# FLODAR_V3.net
KiCad netlist of a schematic drawn in EAGLE
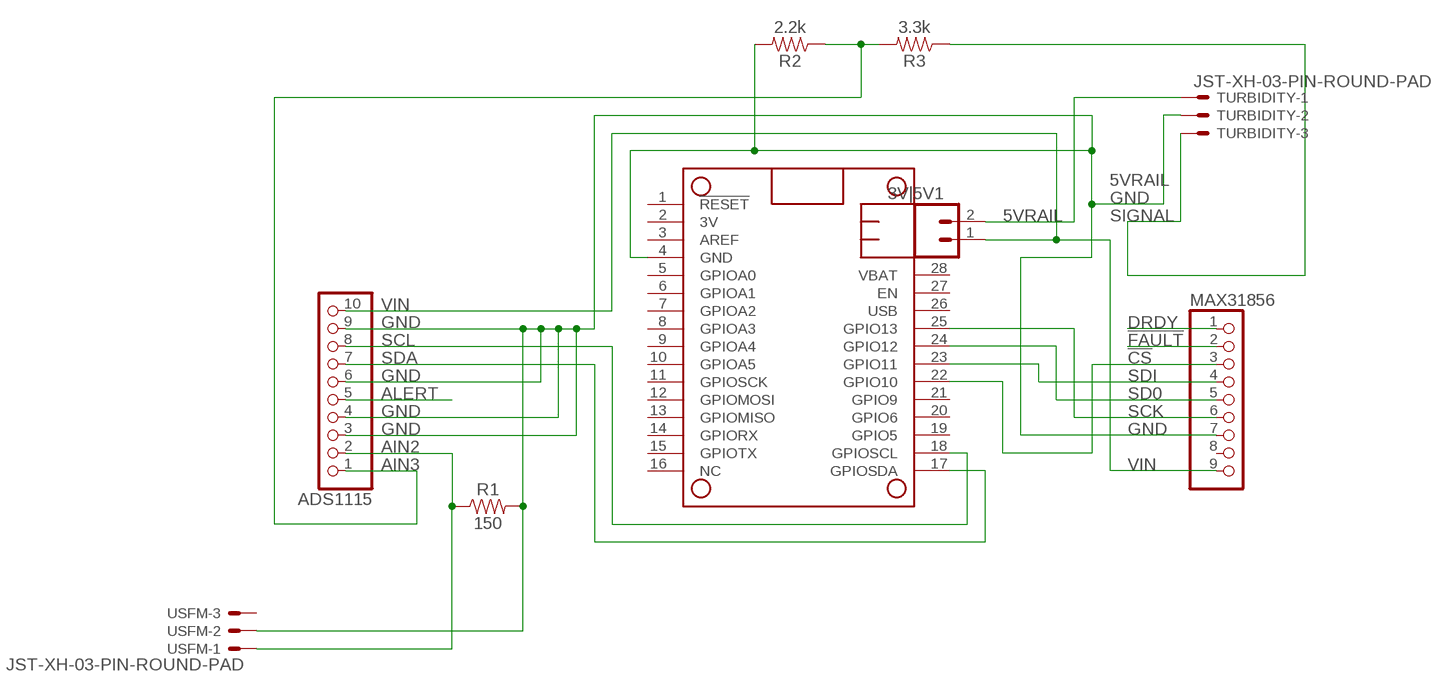
[diagram p0: schematic, sheet 1]

(export (version "E")
  (design (tool "Eeschema 10.0.6"))
  (components
    (comp (ref "3V|5V1")
      (value "CONN_021X02_NO_SILK")
      (footprint "eagle-import:1X02_NO_SILK")
      (libsource (lib "eagle-import") (part "CONN_021X02_NO_SILK"))
    )
    (comp (ref "ADS1115")
      (value "HEADER-1X1070MIL")
      (footprint "eagle-import:1X10_ROUND70")
      (libsource (lib "eagle-import") (part "HEADER-1X1070MIL"))
    )
    (comp (ref "MAX31856")
      (value "HEADER-1X970MIL")
      (footprint "eagle-import:1X09_ROUND_70")
      (libsource (lib "eagle-import") (part "HEADER-1X970MIL"))
    )
    (comp (ref "MS3")
      (value "FEATHERWING")
      (footprint "eagle-import:FEATHERWING")
      (libsource (lib "eagle-import") (part "FEATHERWING"))
    )
    (comp (ref "R1")
      (value "150")
      (footprint "eagle-import:0603")
      (libsource (lib "eagle-import") (part "150OHM-0603-1/10W-1%"))
    )
    (comp (ref "R2")
      (value "2.2k")
      (footprint "eagle-import:0603")
      (libsource (lib "eagle-import") (part "2.2KOHM-0603-1/10W-1%"))
    )
    (comp (ref "R3")
      (value "3.3k")
      (footprint "eagle-import:0603")
      (libsource (lib "eagle-import") (part "3.3KOHM-0603-1/10W-1%"))
    )
    (comp (ref "TURBIDITY")
      (value "JST-XH-03-PIN-ROUND-PAD")
      (footprint "eagle-import:JST-XH-03-PACKAGE-ROUND-PAD")
      (libsource (lib "eagle-import") (part "JST-XH-03-PIN-ROUND-PAD"))
    )
    (comp (ref "USFM")
      (value "JST-XH-03-PIN-ROUND-PAD")
      (footprint "eagle-import:JST-XH-03-PACKAGE-ROUND-PAD")
      (libsource (lib "eagle-import") (part "JST-XH-03-PIN-ROUND-PAD"))
    )
  )
  (nets
    (net (code "1") (name "/3V") (class "Default")
      (node (ref "MS3") (pin "2") (pinfunction "3V_2") (pintype "power_in"))
    )
    (net (code "2") (name "/5VRAIL") (class "Default")
      (node (ref "3V|5V1") (pin "2") (pinfunction "2_2") (pintype "passive"))
      (node (ref "TURBIDITY") (pin "1") (pinfunction "S_1") (pintype "passive"))
    )
    (net (code "3") (name "/AIN2") (class "Default")
      (node (ref "ADS1115") (pin "2") (pinfunction "2_2") (pintype "passive"))
      (node (ref "R1") (pin "1") (pinfunction "1_1") (pintype "passive"))
      (node (ref "USFM") (pin "1") (pinfunction "S_1") (pintype "passive"))
    )
    (net (code "4") (name "/AIN3") (class "Default")
      (node (ref "ADS1115") (pin "1") (pinfunction "1_1") (pintype "passive"))
      (node (ref "R2") (pin "1") (pinfunction "1_1") (pintype "passive"))
      (node (ref "R3") (pin "2") (pinfunction "2_2") (pintype "passive"))
    )
    (net (code "5") (name "/ALERT") (class "Default")
      (node (ref "ADS1115") (pin "5") (pinfunction "5_5") (pintype "passive"))
    )
    (net (code "6") (name "/DRDY") (class "Default")
      (node (ref "MAX31856") (pin "1") (pinfunction "1_1") (pintype "passive"))
    )
    (net (code "7") (name "/GND") (class "Default")
      (node (ref "ADS1115") (pin "3") (pinfunction "3_3") (pintype "passive"))
      (node (ref "ADS1115") (pin "4") (pinfunction "4_4") (pintype "passive"))
      (node (ref "ADS1115") (pin "6") (pinfunction "6_6") (pintype "passive"))
      (node (ref "ADS1115") (pin "9") (pinfunction "9_9") (pintype "passive"))
      (node (ref "MAX31856") (pin "7") (pinfunction "7_7") (pintype "passive"))
      (node (ref "MS3") (pin "4") (pinfunction "GND_4") (pintype "power_in"))
      (node (ref "R1") (pin "2") (pinfunction "2_2") (pintype "passive"))
      (node (ref "R2") (pin "2") (pinfunction "2_2") (pintype "passive"))
      (node (ref "TURBIDITY") (pin "2") (pinfunction "S_2") (pintype "passive"))
      (node (ref "USFM") (pin "2") (pinfunction "S_2") (pintype "passive"))
    )
    (net (code "8") (name "/SCK") (class "Default")
      (node (ref "MAX31856") (pin "6") (pinfunction "6_6") (pintype "passive"))
      (node (ref "MS3") (pin "25") (pinfunction "GPIO13_25") (pintype "bidirectional"))
    )
    (net (code "9") (name "/SCL") (class "Default")
      (node (ref "ADS1115") (pin "8") (pinfunction "8_8") (pintype "passive"))
      (node (ref "MS3") (pin "18") (pinfunction "GPIOSCL_18") (pintype "bidirectional"))
    )
    (net (code "10") (name "/SD0") (class "Default")
      (node (ref "MAX31856") (pin "5") (pinfunction "5_5") (pintype "passive"))
      (node (ref "MS3") (pin "24") (pinfunction "GPIO12_24") (pintype "bidirectional"))
    )
    (net (code "11") (name "/SDA") (class "Default")
      (node (ref "ADS1115") (pin "7") (pinfunction "7_7") (pintype "passive"))
      (node (ref "MS3") (pin "17") (pinfunction "GPIOSDA_17") (pintype "bidirectional"))
    )
    (net (code "12") (name "/SDI") (class "Default")
      (node (ref "MAX31856") (pin "4") (pinfunction "4_4") (pintype "passive"))
      (node (ref "MS3") (pin "23") (pinfunction "GPIO11_23") (pintype "bidirectional"))
    )
    (net (code "13") (name "/SIGNAL") (class "Default")
      (node (ref "R3") (pin "1") (pinfunction "1_1") (pintype "passive"))
      (node (ref "TURBIDITY") (pin "3") (pinfunction "S_3") (pintype "passive"))
    )
    (net (code "14") (name "/USB") (class "Default")
      (node (ref "MS3") (pin "26") (pinfunction "USB_26") (pintype "power_in"))
    )
    (net (code "15") (name "/VBAT") (class "Default")
      (node (ref "MS3") (pin "28") (pinfunction "VBAT_28") (pintype "power_in"))
    )
    (net (code "16") (name "/VIN") (class "Default")
      (node (ref "3V|5V1") (pin "1") (pinfunction "1_1") (pintype "passive"))
      (node (ref "ADS1115") (pin "10") (pinfunction "10_10") (pintype "passive"))
      (node (ref "MAX31856") (pin "9") (pinfunction "9_9") (pintype "passive"))
    )
    (net (code "17") (name "/~{CS}") (class "Default")
      (node (ref "MAX31856") (pin "3") (pinfunction "3_3") (pintype "passive"))
      (node (ref "MS3") (pin "22") (pinfunction "GPIO10_22") (pintype "bidirectional"))
    )
    (net (code "18") (name "/~{FAULT}") (class "Default")
      (node (ref "MAX31856") (pin "2") (pinfunction "2_2") (pintype "passive"))
    )
    (net (code "19") (name "unconnected-(MAX31856-Pad8)") (class "Default")
      (node (ref "MAX31856") (pin "8") (pinfunction "8_8") (pintype "passive"))
    )
    (net (code "20") (name "unconnected-(MS3-AREF-Pad3)") (class "Default")
      (node (ref "MS3") (pin "3") (pinfunction "AREF_3") (pintype "passive"))
    )
    (net (code "21") (name "unconnected-(MS3-EN-Pad27)") (class "Default")
      (node (ref "MS3") (pin "27") (pinfunction "EN_27") (pintype "passive"))
    )
    (net (code "22") (name "unconnected-(MS3-GPIO5-Pad19)") (class "Default")
      (node (ref "MS3") (pin "19") (pinfunction "GPIO5_19") (pintype "bidirectional"))
    )
    (net (code "23") (name "unconnected-(MS3-GPIO6-Pad20)") (class "Default")
      (node (ref "MS3") (pin "20") (pinfunction "GPIO6_20") (pintype "bidirectional"))
    )
    (net (code "24") (name "unconnected-(MS3-GPIO9-Pad21)") (class "Default")
      (node (ref "MS3") (pin "21") (pinfunction "GPIO9_21") (pintype "bidirectional"))
    )
    (net (code "25") (name "unconnected-(MS3-GPIOA0-Pad5)") (class "Default")
      (node (ref "MS3") (pin "5") (pinfunction "GPIOA0_5") (pintype "bidirectional"))
    )
    (net (code "26") (name "unconnected-(MS3-GPIOA1-Pad6)") (class "Default")
      (node (ref "MS3") (pin "6") (pinfunction "GPIOA1_6") (pintype "bidirectional"))
    )
    (net (code "27") (name "unconnected-(MS3-GPIOA2-Pad7)") (class "Default")
      (node (ref "MS3") (pin "7") (pinfunction "GPIOA2_7") (pintype "bidirectional"))
    )
    (net (code "28") (name "unconnected-(MS3-GPIOA3-Pad8)") (class "Default")
      (node (ref "MS3") (pin "8") (pinfunction "GPIOA3_8") (pintype "bidirectional"))
    )
    (net (code "29") (name "unconnected-(MS3-GPIOA4-Pad9)") (class "Default")
      (node (ref "MS3") (pin "9") (pinfunction "GPIOA4_9") (pintype "bidirectional"))
    )
    (net (code "30") (name "unconnected-(MS3-GPIOA5-Pad10)") (class "Default")
      (node (ref "MS3") (pin "10") (pinfunction "GPIOA5_10") (pintype "bidirectional"))
    )
    (net (code "31") (name "unconnected-(MS3-GPIOMISO-Pad13)") (class "Default")
      (node (ref "MS3") (pin "13") (pinfunction "GPIOMISO_13") (pintype "bidirectional"))
    )
    (net (code "32") (name "unconnected-(MS3-GPIOMOSI-Pad12)") (class "Default")
      (node (ref "MS3") (pin "12") (pinfunction "GPIOMOSI_12") (pintype "bidirectional"))
    )
    (net (code "33") (name "unconnected-(MS3-GPIORX-Pad14)") (class "Default")
      (node (ref "MS3") (pin "14") (pinfunction "GPIORX_14") (pintype "bidirectional"))
    )
    (net (code "34") (name "unconnected-(MS3-GPIOSCK-Pad11)") (class "Default")
      (node (ref "MS3") (pin "11") (pinfunction "GPIOSCK_11") (pintype "bidirectional"))
    )
    (net (code "35") (name "unconnected-(MS3-GPIOTX-Pad15)") (class "Default")
      (node (ref "MS3") (pin "15") (pinfunction "GPIOTX_15") (pintype "bidirectional"))
    )
    (net (code "36") (name "unconnected-(MS3-NC-Pad16)") (class "Default")
      (node (ref "MS3") (pin "16") (pinfunction "NC_16") (pintype "passive"))
    )
    (net (code "37") (name "unconnected-(MS3-~{RESET}-Pad1)") (class "Default")
      (node (ref "MS3") (pin "1") (pinfunction "~{RESET}_1") (pintype "input"))
    )
    (net (code "38") (name "unconnected-(USFMC-S-Pad3)") (class "Default")
      (node (ref "USFM") (pin "3") (pinfunction "S_3") (pintype "passive"))
    )
  )
)
